# sensor_M_Pascal_Darmawan_21507334050.net
KiCad netlist of a schematic drawn in EAGLE
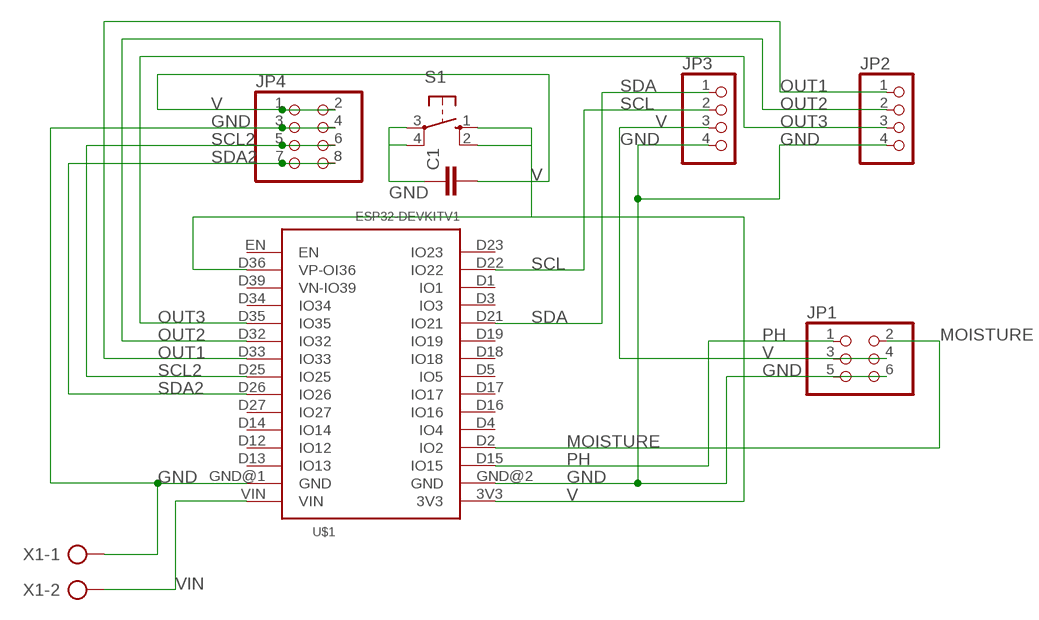
[diagram p0: schematic, sheet 1]

(export (version "E")
  (design (tool "Eeschema 10.0.6"))
  (components
    (comp (ref "C1")
      (value "C-EU050-030X075")
      (footprint "eagle-import:C050-030X075")
      (libsource (lib "eagle-import") (part "C-EU050-030X075"))
    )
    (comp (ref "JP1")
      (value "PINHD-2X3")
      (footprint "eagle-import:2X03")
      (libsource (lib "eagle-import") (part "PINHD-2X3"))
    )
    (comp (ref "JP2")
      (value "PINHD-1X4")
      (footprint "eagle-import:1X04")
      (libsource (lib "eagle-import") (part "PINHD-1X4"))
    )
    (comp (ref "JP3")
      (value "PINHD-1X4")
      (footprint "eagle-import:1X04")
      (libsource (lib "eagle-import") (part "PINHD-1X4"))
    )
    (comp (ref "JP4")
      (value "PINHD-2X4")
      (footprint "eagle-import:2X04")
      (libsource (lib "eagle-import") (part "PINHD-2X4"))
    )
    (comp (ref "S1")
      (value "10-XX")
      (footprint "eagle-import:B3F-10XX")
      (fields (field (name "MPN") "B3F-1000"))
      (libsource (lib "eagle-import") (part "10-XX"))
    )
    (comp (ref "U$1")
      (value "ESP32DEVKITV1")
      (footprint "eagle-import:ESP32-DEVKITV1")
      (libsource (lib "eagle-import") (part "ESP32DEVKITV1"))
    )
    (comp (ref "X1")
      (value "AK300/2")
      (footprint "eagle-import:AK300_2")
      (libsource (lib "eagle-import") (part "AK300/2"))
    )
  )
  (nets
    (net (code "1") (name "/GND") (class "Default")
      (node (ref "C1") (pin "1") (pinfunction "1_1") (pintype "passive"))
      (node (ref "JP1") (pin "5") (pinfunction "5_5") (pintype "passive"))
      (node (ref "JP1") (pin "6") (pinfunction "6_6") (pintype "passive"))
      (node (ref "JP2") (pin "4") (pinfunction "4_4") (pintype "passive"))
      (node (ref "JP3") (pin "4") (pinfunction "4_4") (pintype "passive"))
      (node (ref "JP4") (pin "3") (pinfunction "3_3") (pintype "passive"))
      (node (ref "JP4") (pin "4") (pinfunction "4_4") (pintype "passive"))
      (node (ref "S1") (pin "3") (pinfunction "P_3") (pintype "passive"))
      (node (ref "S1") (pin "4") (pinfunction "P1_4") (pintype "passive"))
      (node (ref "U$1") (pin "GND@1") (pinfunction "GND_GND@1") (pintype "bidirectional"))
      (node (ref "U$1") (pin "GND@2") (pinfunction "GND_GND@2") (pintype "bidirectional"))
      (node (ref "X1") (pin "1") (pinfunction "KL_1") (pintype "passive"))
    )
    (net (code "2") (name "/MOISTURE") (class "Default")
      (node (ref "JP1") (pin "2") (pinfunction "2_2") (pintype "passive"))
      (node (ref "U$1") (pin "D2") (pinfunction "IO2_D2") (pintype "bidirectional"))
    )
    (net (code "3") (name "/OUT1") (class "Default")
      (node (ref "JP2") (pin "1") (pinfunction "1_1") (pintype "passive"))
      (node (ref "U$1") (pin "D33") (pinfunction "IO33_D33") (pintype "bidirectional"))
    )
    (net (code "4") (name "/OUT2") (class "Default")
      (node (ref "JP2") (pin "2") (pinfunction "2_2") (pintype "passive"))
      (node (ref "U$1") (pin "D32") (pinfunction "IO32_D32") (pintype "bidirectional"))
    )
    (net (code "5") (name "/OUT3") (class "Default")
      (node (ref "JP2") (pin "3") (pinfunction "3_3") (pintype "passive"))
      (node (ref "U$1") (pin "D35") (pinfunction "IO35_D35") (pintype "bidirectional"))
    )
    (net (code "6") (name "/PH") (class "Default")
      (node (ref "JP1") (pin "1") (pinfunction "1_1") (pintype "passive"))
      (node (ref "U$1") (pin "D15") (pinfunction "IO15_D15") (pintype "bidirectional"))
    )
    (net (code "7") (name "/SCL") (class "Default")
      (node (ref "JP3") (pin "2") (pinfunction "2_2") (pintype "passive"))
      (node (ref "U$1") (pin "D22") (pinfunction "IO22_D22") (pintype "bidirectional"))
    )
    (net (code "8") (name "/SCL2") (class "Default")
      (node (ref "JP4") (pin "5") (pinfunction "5_5") (pintype "passive"))
      (node (ref "JP4") (pin "6") (pinfunction "6_6") (pintype "passive"))
      (node (ref "U$1") (pin "D25") (pinfunction "IO25_D25") (pintype "bidirectional"))
    )
    (net (code "9") (name "/SDA") (class "Default")
      (node (ref "JP3") (pin "1") (pinfunction "1_1") (pintype "passive"))
      (node (ref "U$1") (pin "D21") (pinfunction "IO21_D21") (pintype "bidirectional"))
    )
    (net (code "10") (name "/SDA2") (class "Default")
      (node (ref "JP4") (pin "7") (pinfunction "7_7") (pintype "passive"))
      (node (ref "JP4") (pin "8") (pinfunction "8_8") (pintype "passive"))
      (node (ref "U$1") (pin "D26") (pinfunction "IO26_D26") (pintype "bidirectional"))
    )
    (net (code "11") (name "/V") (class "Default")
      (node (ref "C1") (pin "2") (pinfunction "2_2") (pintype "passive"))
      (node (ref "JP1") (pin "3") (pinfunction "3_3") (pintype "passive"))
      (node (ref "JP1") (pin "4") (pinfunction "4_4") (pintype "passive"))
      (node (ref "JP3") (pin "3") (pinfunction "3_3") (pintype "passive"))
      (node (ref "JP4") (pin "1") (pinfunction "1_1") (pintype "passive"))
      (node (ref "JP4") (pin "2") (pinfunction "2_2") (pintype "passive"))
      (node (ref "S1") (pin "1") (pinfunction "S_1") (pintype "passive"))
      (node (ref "S1") (pin "2") (pinfunction "S1_2") (pintype "passive"))
      (node (ref "U$1") (pin "3V3") (pinfunction "3V3_3V3") (pintype "bidirectional"))
      (node (ref "U$1") (pin "D36") (pinfunction "VP-OI36_D36") (pintype "bidirectional"))
    )
    (net (code "12") (name "/VIN") (class "Default")
      (node (ref "U$1") (pin "VIN") (pinfunction "VIN_VIN") (pintype "bidirectional"))
      (node (ref "X1") (pin "2") (pinfunction "KL_2") (pintype "passive"))
    )
    (net (code "13") (name "unconnected-(U$1-IO1-PadD1)") (class "Default")
      (node (ref "U$1") (pin "D1") (pinfunction "IO1_D1") (pintype "bidirectional"))
    )
    (net (code "14") (name "unconnected-(U$1-IO3-PadD3)") (class "Default")
      (node (ref "U$1") (pin "D3") (pinfunction "IO3_D3") (pintype "bidirectional"))
    )
    (net (code "15") (name "unconnected-(U$1-IO4-PadD4)") (class "Default")
      (node (ref "U$1") (pin "D4") (pinfunction "IO4_D4") (pintype "bidirectional"))
    )
    (net (code "16") (name "unconnected-(U$1-IO5-PadD5)") (class "Default")
      (node (ref "U$1") (pin "D5") (pinfunction "IO5_D5") (pintype "bidirectional"))
    )
    (net (code "17") (name "unconnected-(U$1-IO12-PadD12)") (class "Default")
      (node (ref "U$1") (pin "D12") (pinfunction "IO12_D12") (pintype "bidirectional"))
    )
    (net (code "18") (name "unconnected-(U$1-IO13-PadD13)") (class "Default")
      (node (ref "U$1") (pin "D13") (pinfunction "IO13_D13") (pintype "bidirectional"))
    )
    (net (code "19") (name "unconnected-(U$1-IO14-PadD14)") (class "Default")
      (node (ref "U$1") (pin "D14") (pinfunction "IO14_D14") (pintype "bidirectional"))
    )
    (net (code "20") (name "unconnected-(U$1-IO16-PadD16)") (class "Default")
      (node (ref "U$1") (pin "D16") (pinfunction "IO16_D16") (pintype "bidirectional"))
    )
    (net (code "21") (name "unconnected-(U$1-IO17-PadD17)") (class "Default")
      (node (ref "U$1") (pin "D17") (pinfunction "IO17_D17") (pintype "bidirectional"))
    )
    (net (code "22") (name "unconnected-(U$1-IO18-PadD18)") (class "Default")
      (node (ref "U$1") (pin "D18") (pinfunction "IO18_D18") (pintype "bidirectional"))
    )
    (net (code "23") (name "unconnected-(U$1-IO19-PadD19)") (class "Default")
      (node (ref "U$1") (pin "D19") (pinfunction "IO19_D19") (pintype "bidirectional"))
    )
    (net (code "24") (name "unconnected-(U$1-IO23-PadD23)") (class "Default")
      (node (ref "U$1") (pin "D23") (pinfunction "IO23_D23") (pintype "bidirectional"))
    )
    (net (code "25") (name "unconnected-(U$1-IO27-PadD27)") (class "Default")
      (node (ref "U$1") (pin "D27") (pinfunction "IO27_D27") (pintype "bidirectional"))
    )
    (net (code "26") (name "unconnected-(U$1-IO34-PadD34)") (class "Default")
      (node (ref "U$1") (pin "D34") (pinfunction "IO34_D34") (pintype "bidirectional"))
    )
    (net (code "27") (name "unconnected-(U$1-PadEN)") (class "Default")
      (node (ref "U$1") (pin "EN") (pinfunction "EN_EN") (pintype "bidirectional"))
    )
    (net (code "28") (name "unconnected-(U$1-VN-IO39-PadD39)") (class "Default")
      (node (ref "U$1") (pin "D39") (pinfunction "VN-IO39_D39") (pintype "bidirectional"))
    )
  )
)
